# 16_40PIN_Connector.net
KiCad netlist of a schematic drawn in Altium Designer
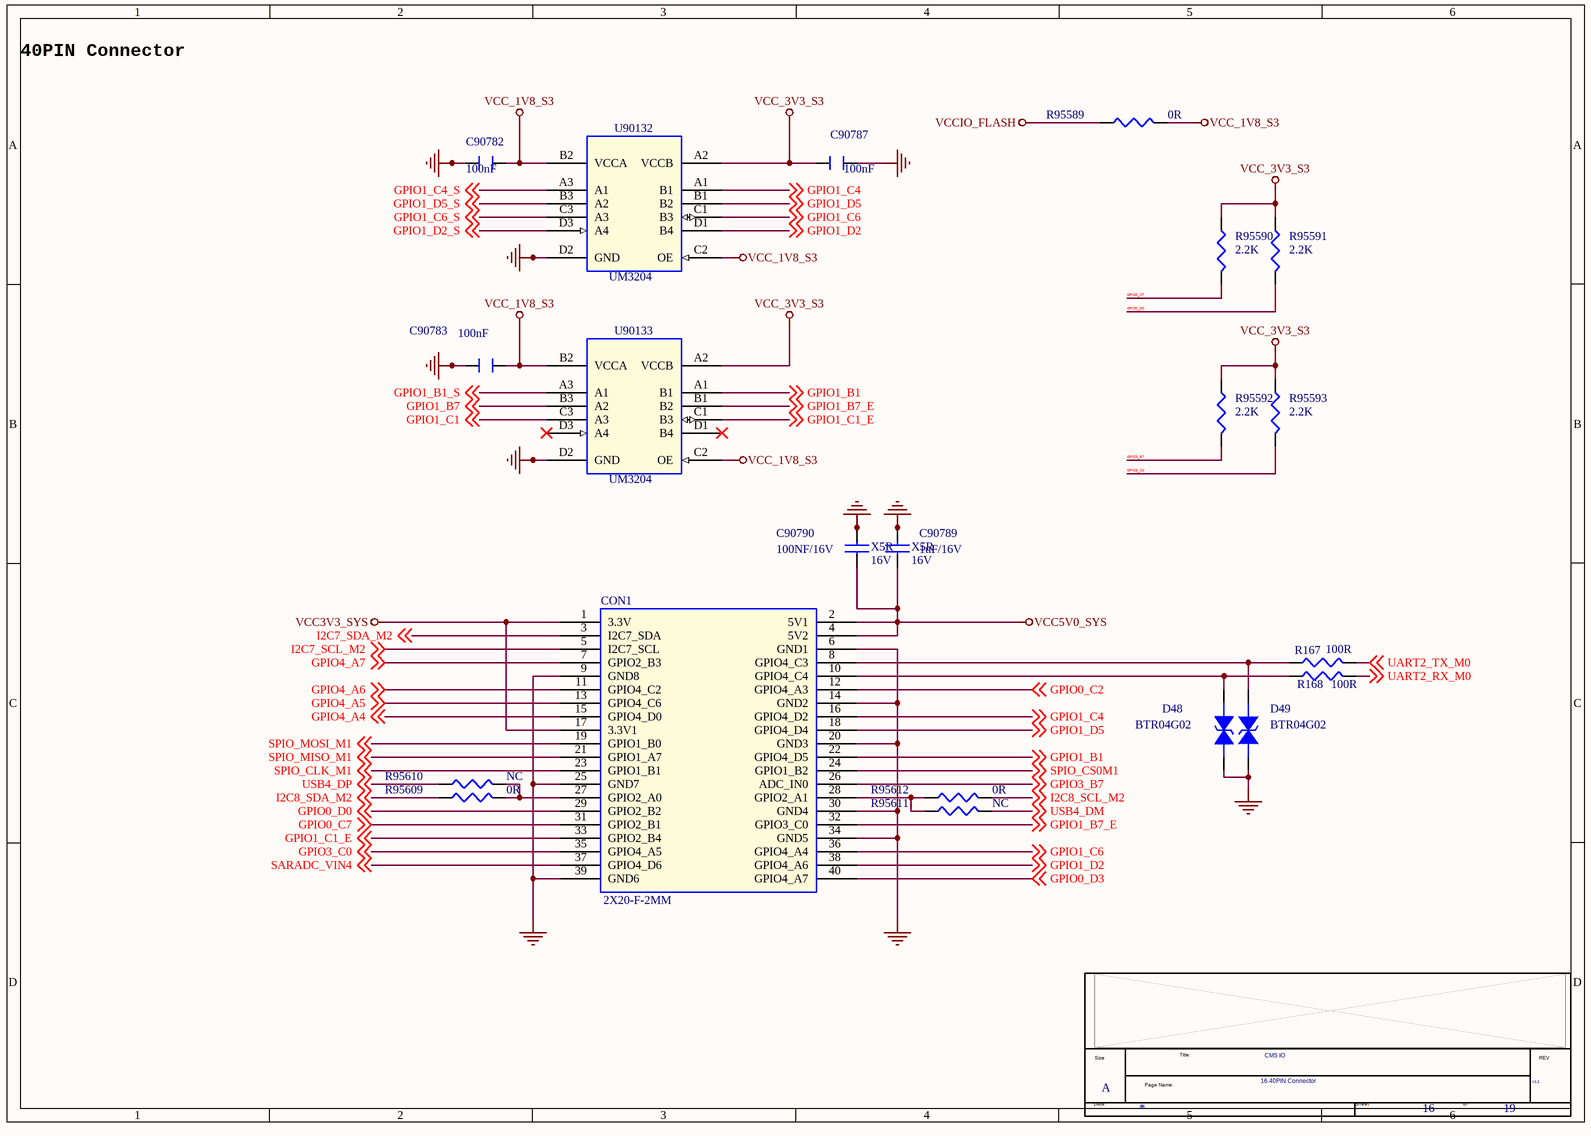
[diagram p0: 16_40PIN_Connector.SchDoc]

(export (version "E")
  (design (tool "Eeschema 10.0.6"))
  (components
    (comp (ref "*")
      (value "radxa_1010")
      (fields
        (field (name "DOC") "16.40PIN Connector")
        (field (name "REVCODE") "V2.2")
        (field (name "TITLE") "CM5 IO")
        (field (name "PAGE SIZE") "A")
        (field (name "PAGE NUMBER") "16")
        (field (name "PAGE COUNT") "19")
      )
      (libsource (lib "*") (part "radxa_1010"))
    )
    (comp (ref "C90782") (value "100nF") (footprint "C0402") (libsource (lib "*") (part "CAPACITOR_0")))
    (comp (ref "C90783") (value "100nF") (footprint "C0402") (libsource (lib "*") (part "CAPACITOR_0")))
    (comp (ref "C90787") (value "100nF") (footprint "C0402") (libsource (lib "*") (part "CAPACITOR_0")))
    (comp (ref "C90789")
      (value "1uF/16V")
      (footprint "C0402")
      (description "cap,1.00uF,+/-10%,16V,X5R,C0402")
      (fields
        (field (name "VOLTAGE") "16V")
        (field (name "DIELECTRIC") "X5R")
        (field (name "MANUFACTURER") "TDK")
        (field (name "TOLERANCE") "10%")
        (field (name "CREATED BY") "JJJ")
      )
      (libsource (lib "*") (part "CAP NP_0"))
    )
    (comp (ref "C90790")
      (value "100NF/16V")
      (footprint "C0402")
      (description "cap,100.00nF,+/-10%,16V,X5R,C0402")
      (fields
        (field (name "VOLTAGE") "16V")
        (field (name "DIELECTRIC") "X5R")
        (field (name "TOLERANCE") "10%")
        (field (name "MANUFACTURER") "TDK")
        (field (name "CREATED BY") "JJJ")
      )
      (libsource (lib "*") (part "CAP NP_0"))
    )
    (comp (ref "CON1")
      (value "2X20-F-2MM")
      (footprint "DIP40PIN_2D54MM")
      (libsource (lib "*") (part "CN_0_Dup1"))
    )
    (comp (ref "D48")
      (value "BTR04G02")
      (footprint "ESD0402_1XD5")
      (description "1-Line, Bi-directional, Transient Voltage Suppressors.17.5pF.")
      (fields (field (name "MANUFACTURER") "WillSemi(韦尔半导体)") (field (name "CREATED BY") "JJJ"))
      (libsource (lib "*") (part "DIODE BI_DIR TRIG_2"))
    )
    (comp (ref "D49")
      (value "BTR04G02")
      (footprint "ESD0402_1XD5")
      (description "1-Line, Bi-directional, Transient Voltage Suppressors.17.5pF.")
      (fields (field (name "MANUFACTURER") "WillSemi(韦尔半导体)") (field (name "CREATED BY") "JJJ"))
      (libsource (lib "*") (part "DIODE BI_DIR TRIG_2"))
    )
    (comp (ref "R167")
      (value "100R")
      (footprint "R0402")
      (description "通用厚膜电阻,100R,+/-5%,R0402,1/16W.")
      (fields
        (field (name "TOLERANCE") "5%")
        (field (name "MANUFACTURER") "YAGEO")
        (field (name "CREATED BY") "YTL")
      )
      (libsource (lib "*") (part "RESISTOR_0_Dup3"))
    )
    (comp (ref "R168")
      (value "100R")
      (footprint "R0402")
      (description "通用厚膜电阻,100R,+/-5%,R0402,1/16W.")
      (fields
        (field (name "TOLERANCE") "5%")
        (field (name "MANUFACTURER") "YAGEO")
        (field (name "CREATED BY") "YTL")
      )
      (libsource (lib "*") (part "RESISTOR_0_Dup3"))
    )
    (comp (ref "R95589")
      (value "0R")
      (footprint "R0402")
      (description "通用厚膜电阻,2K2,+/-5%,R0402,1/16W.")
      (fields
        (field (name "TOLERANCE") "5%")
        (field (name "MANUFACTURER") "YAGEO")
        (field (name "CREATED BY") "YTL")
      )
      (libsource (lib "*") (part "RESISTOR_3"))
    )
    (comp (ref "R95590")
      (value "2.2K")
      (footprint "R0402")
      (description "通用厚膜电阻,2K2,+/-5%,R0402,1/16W.")
      (fields
        (field (name "TOLERANCE") "5%")
        (field (name "MANUFACTURER") "YAGEO")
        (field (name "CREATED BY") "YTL")
      )
      (libsource (lib "*") (part "RESISTOR_3"))
    )
    (comp (ref "R95591")
      (value "2.2K")
      (footprint "R0402")
      (description "通用厚膜电阻,2K2,+/-5%,R0402,1/16W.")
      (fields
        (field (name "TOLERANCE") "5%")
        (field (name "MANUFACTURER") "YAGEO")
        (field (name "CREATED BY") "YTL")
      )
      (libsource (lib "*") (part "RESISTOR_3"))
    )
    (comp (ref "R95592")
      (value "2.2K")
      (footprint "R0402")
      (description "通用厚膜电阻,2K2,+/-5%,R0402,1/16W.")
      (fields
        (field (name "TOLERANCE") "5%")
        (field (name "MANUFACTURER") "YAGEO")
        (field (name "CREATED BY") "YTL")
      )
      (libsource (lib "*") (part "RESISTOR_3"))
    )
    (comp (ref "R95593")
      (value "2.2K")
      (footprint "R0402")
      (description "通用厚膜电阻,2K2,+/-5%,R0402,1/16W.")
      (fields
        (field (name "TOLERANCE") "5%")
        (field (name "MANUFACTURER") "YAGEO")
        (field (name "CREATED BY") "YTL")
      )
      (libsource (lib "*") (part "RESISTOR_3"))
    )
    (comp (ref "R95609")
      (value "0R")
      (footprint "R0402")
      (description "通用厚膜电阻,2K2,+/-5%,R0402,1/16W.")
      (fields
        (field (name "TOLERANCE") "5%")
        (field (name "MANUFACTURER") "YAGEO")
        (field (name "CREATED BY") "YTL")
      )
      (libsource (lib "*") (part "RESISTOR_3"))
    )
    (comp (ref "R95610")
      (value "NC")
      (footprint "R0402")
      (description "通用厚膜电阻,2K2,+/-5%,R0402,1/16W.")
      (fields
        (field (name "TOLERANCE") "5%")
        (field (name "MANUFACTURER") "YAGEO")
        (field (name "CREATED BY") "YTL")
      )
      (libsource (lib "*") (part "RESISTOR_3"))
    )
    (comp (ref "R95611")
      (value "NC")
      (footprint "R0402")
      (description "通用厚膜电阻,2K2,+/-5%,R0402,1/16W.")
      (fields
        (field (name "TOLERANCE") "5%")
        (field (name "MANUFACTURER") "YAGEO")
        (field (name "CREATED BY") "YTL")
      )
      (libsource (lib "*") (part "RESISTOR_3"))
    )
    (comp (ref "R95612")
      (value "0R")
      (footprint "R0402")
      (description "通用厚膜电阻,2K2,+/-5%,R0402,1/16W.")
      (fields
        (field (name "TOLERANCE") "5%")
        (field (name "MANUFACTURER") "YAGEO")
        (field (name "CREATED BY") "YTL")
      )
      (libsource (lib "*") (part "RESISTOR_3"))
    )
    (comp (ref "U90132")
      (value "UM3204")
      (footprint "CSP-12")
      (description "4-bit Bi-directional Level Shifter  UM3204H")
      (fields (field (name "PART NUMBER") "PI4ULS5V104GAEX"))
      (libsource (lib "*") (part "MP2610_0"))
    )
    (comp (ref "U90133")
      (value "UM3204")
      (footprint "CSP-12")
      (description "4-bit Bi-directional Level Shifter  UM3204H")
      (fields (field (name "PART NUMBER") "PI4ULS5V104GAEX"))
      (libsource (lib "*") (part "MP2610_0"))
    )
  )
  (nets
    (net (code "1") (name "GND") (class "Default")
      (node (ref "C90782") (pin "1") (pinfunction "1_1") (pintype "passive"))
      (node (ref "C90783") (pin "1") (pinfunction "1_1") (pintype "passive"))
      (node (ref "C90787") (pin "1") (pinfunction "1_1") (pintype "passive"))
      (node (ref "C90789") (pin "2") (pinfunction "2_2") (pintype "passive"))
      (node (ref "C90790") (pin "2") (pinfunction "2_2") (pintype "passive"))
      (node (ref "CON1") (pin "14") (pinfunction "GND2_14") (pintype "passive"))
      (node (ref "CON1") (pin "20") (pinfunction "GND3_20") (pintype "passive"))
      (node (ref "CON1") (pin "25") (pinfunction "GND7_25") (pintype "passive"))
      (node (ref "CON1") (pin "30") (pinfunction "GND4_30") (pintype "passive"))
      (node (ref "CON1") (pin "34") (pinfunction "GND5_34") (pintype "passive"))
      (node (ref "CON1") (pin "39") (pinfunction "GND6_39") (pintype "passive"))
      (node (ref "CON1") (pin "6") (pinfunction "GND1_6") (pintype "passive"))
      (node (ref "CON1") (pin "9") (pinfunction "GND8_9") (pintype "passive"))
      (node (ref "D48") (pin "1") (pinfunction "1_1") (pintype "passive"))
      (node (ref "D49") (pin "1") (pinfunction "1_1") (pintype "passive"))
      (node (ref "U90132") (pin "D2") (pinfunction "GND_D2") (pintype "power_in"))
      (node (ref "U90133") (pin "D2") (pinfunction "GND_D2") (pintype "power_in"))
    )
    (net (code "2") (name "GPIO0_C2") (class "Default")
      (node (ref "CON1") (pin "12") (pinfunction "GPIO4_A3_12") (pintype "passive"))
    )
    (net (code "3") (name "GPIO0_C7") (class "Default")
      (node (ref "CON1") (pin "31") (pinfunction "GPIO2_B1_31") (pintype "passive"))
      (node (ref "R95590") (pin "2") (pinfunction "2_2") (pintype "passive"))
    )
    (net (code "4") (name "GPIO0_D0") (class "Default")
      (node (ref "CON1") (pin "29") (pinfunction "GPIO2_B2_29") (pintype "passive"))
      (node (ref "R95591") (pin "2") (pinfunction "2_2") (pintype "passive"))
    )
    (net (code "5") (name "GPIO0_D3") (class "Default")
      (node (ref "CON1") (pin "40") (pinfunction "GPIO4_A7_40") (pintype "passive"))
    )
    (net (code "6") (name "GPIO1_B1") (class "Default")
      (node (ref "CON1") (pin "22") (pinfunction "GPIO4_D5_22") (pintype "passive"))
      (node (ref "U90133") (pin "A1") (pinfunction "B1_A1") (pintype "tri_state"))
    )
    (net (code "7") (name "GPIO1_B1_S") (class "Default")
      (node (ref "U90133") (pin "A3") (pinfunction "A1_A3") (pintype "tri_state"))
    )
    (net (code "8") (name "GPIO1_B7") (class "Default")
      (node (ref "U90133") (pin "B3") (pinfunction "A2_B3") (pintype "tri_state"))
    )
    (net (code "9") (name "GPIO1_B7_E") (class "Default")
      (node (ref "CON1") (pin "32") (pinfunction "GPIO3_C0_32") (pintype "passive"))
      (node (ref "U90133") (pin "B1") (pinfunction "B2_B1") (pintype "tri_state"))
    )
    (net (code "10") (name "GPIO1_C1") (class "Default")
      (node (ref "U90133") (pin "C3") (pinfunction "A3_C3") (pintype "tri_state"))
    )
    (net (code "11") (name "GPIO1_C1_E") (class "Default")
      (node (ref "CON1") (pin "33") (pinfunction "GPIO2_B4_33") (pintype "passive"))
      (node (ref "U90133") (pin "C1") (pinfunction "B3_C1") (pintype "bidirectional"))
    )
    (net (code "12") (name "GPIO1_C4") (class "Default")
      (node (ref "CON1") (pin "16") (pinfunction "GPIO4_D2_16") (pintype "passive"))
      (node (ref "U90132") (pin "A1") (pinfunction "B1_A1") (pintype "tri_state"))
    )
    (net (code "13") (name "GPIO1_C4_S") (class "Default")
      (node (ref "U90132") (pin "A3") (pinfunction "A1_A3") (pintype "tri_state"))
    )
    (net (code "14") (name "GPIO1_C6") (class "Default")
      (node (ref "CON1") (pin "36") (pinfunction "GPIO4_A4_36") (pintype "passive"))
      (node (ref "U90132") (pin "C1") (pinfunction "B3_C1") (pintype "bidirectional"))
    )
    (net (code "15") (name "GPIO1_C6_S") (class "Default")
      (node (ref "U90132") (pin "C3") (pinfunction "A3_C3") (pintype "tri_state"))
    )
    (net (code "16") (name "GPIO1_D2") (class "Default")
      (node (ref "CON1") (pin "38") (pinfunction "GPIO4_A6_38") (pintype "passive"))
      (node (ref "U90132") (pin "D1") (pinfunction "B4_D1") (pintype "tri_state"))
    )
    (net (code "17") (name "GPIO1_D2_S") (class "Default")
      (node (ref "U90132") (pin "D3") (pinfunction "A4_D3") (pintype "input"))
    )
    (net (code "18") (name "GPIO1_D5") (class "Default")
      (node (ref "CON1") (pin "18") (pinfunction "GPIO4_D4_18") (pintype "passive"))
      (node (ref "U90132") (pin "B1") (pinfunction "B2_B1") (pintype "tri_state"))
    )
    (net (code "19") (name "GPIO1_D5_S") (class "Default")
      (node (ref "U90132") (pin "B3") (pinfunction "A2_B3") (pintype "tri_state"))
    )
    (net (code "20") (name "GPIO3_B7") (class "Default")
      (node (ref "CON1") (pin "26") (pinfunction "ADC_IN0_26") (pintype "passive"))
      (node (ref "R95592") (pin "2") (pinfunction "2_2") (pintype "passive"))
    )
    (net (code "21") (name "GPIO3_C0") (class "Default")
      (node (ref "CON1") (pin "35") (pinfunction "GPIO4_A5_35") (pintype "passive"))
      (node (ref "R95593") (pin "2") (pinfunction "2_2") (pintype "passive"))
    )
    (net (code "22") (name "GPIO4_A4") (class "Default")
      (node (ref "CON1") (pin "15") (pinfunction "GPIO4_D0_15") (pintype "passive"))
    )
    (net (code "23") (name "GPIO4_A5") (class "Default")
      (node (ref "CON1") (pin "13") (pinfunction "GPIO4_C6_13") (pintype "passive"))
    )
    (net (code "24") (name "GPIO4_A6") (class "Default")
      (node (ref "CON1") (pin "11") (pinfunction "GPIO4_C2_11") (pintype "passive"))
    )
    (net (code "25") (name "GPIO4_A7") (class "Default")
      (node (ref "CON1") (pin "7") (pinfunction "GPIO2_B3_7") (pintype "passive"))
    )
    (net (code "26") (name "I2C7_SCL_M2") (class "Default")
      (node (ref "CON1") (pin "5") (pinfunction "I2C7_SCL_5") (pintype "passive"))
    )
    (net (code "27") (name "I2C7_SDA_M2") (class "Default")
      (node (ref "CON1") (pin "3") (pinfunction "I2C7_SDA_3") (pintype "passive"))
    )
    (net (code "28") (name "I2C8_SCL_M2") (class "Default")
      (node (ref "R95612") (pin "2") (pinfunction "2_2") (pintype "passive"))
    )
    (net (code "29") (name "I2C8_SDA_M2") (class "Default")
      (node (ref "R95609") (pin "1") (pinfunction "1_1") (pintype "passive"))
    )
    (net (code "30") (name "Net-(CON1-GPIO2_A0)") (class "Default")
      (node (ref "CON1") (pin "27") (pinfunction "GPIO2_A0_27") (pintype "passive"))
      (node (ref "R95609") (pin "2") (pinfunction "2_2") (pintype "passive"))
      (node (ref "R95610") (pin "2") (pinfunction "2_2") (pintype "passive"))
    )
    (net (code "31") (name "Net-(CON1-GPIO2_A1)") (class "Default")
      (node (ref "CON1") (pin "28") (pinfunction "GPIO2_A1_28") (pintype "passive"))
      (node (ref "R95611") (pin "1") (pinfunction "1_1") (pintype "passive"))
      (node (ref "R95612") (pin "1") (pinfunction "1_1") (pintype "passive"))
    )
    (net (code "32") (name "Net-(CON1-GPIO4_C3)") (class "Default")
      (node (ref "CON1") (pin "8") (pinfunction "GPIO4_C3_8") (pintype "passive"))
      (node (ref "D49") (pin "2") (pinfunction "2_2") (pintype "passive"))
      (node (ref "R167") (pin "1") (pinfunction "1_1") (pintype "passive"))
    )
    (net (code "33") (name "Net-(CON1-GPIO4_C4)") (class "Default")
      (node (ref "CON1") (pin "10") (pinfunction "GPIO4_C4_10") (pintype "passive"))
      (node (ref "D48") (pin "2") (pinfunction "2_2") (pintype "passive"))
      (node (ref "R168") (pin "1") (pinfunction "1_1") (pintype "passive"))
    )
    (net (code "34") (name "SARADC_VIN4") (class "Default")
      (node (ref "CON1") (pin "37") (pinfunction "GPIO4_D6_37") (pintype "passive"))
    )
    (net (code "35") (name "SPIO_CLK_M1") (class "Default")
      (node (ref "CON1") (pin "23") (pinfunction "GPIO1_B1_23") (pintype "passive"))
    )
    (net (code "36") (name "SPIO_CS0M1") (class "Default")
      (node (ref "CON1") (pin "24") (pinfunction "GPIO1_B2_24") (pintype "passive"))
    )
    (net (code "37") (name "SPIO_MISO_M1") (class "Default")
      (node (ref "CON1") (pin "21") (pinfunction "GPIO1_A7_21") (pintype "passive"))
    )
    (net (code "38") (name "SPIO_MOSI_M1") (class "Default")
      (node (ref "CON1") (pin "19") (pinfunction "GPIO1_B0_19") (pintype "passive"))
    )
    (net (code "39") (name "UART2_RX_M0") (class "Default")
      (node (ref "R168") (pin "2") (pinfunction "2_2") (pintype "passive"))
    )
    (net (code "40") (name "UART2_TX_M0") (class "Default")
      (node (ref "R167") (pin "2") (pinfunction "2_2") (pintype "passive"))
    )
    (net (code "41") (name "USB4_DM") (class "Default")
      (node (ref "R95611") (pin "2") (pinfunction "2_2") (pintype "passive"))
    )
    (net (code "42") (name "USB4_DP") (class "Default")
      (node (ref "R95610") (pin "1") (pinfunction "1_1") (pintype "passive"))
    )
    (net (code "43") (name "VCC3V3_SYS") (class "Default")
      (node (ref "CON1") (pin "1") (pinfunction "3.3V_1") (pintype "passive"))
      (node (ref "CON1") (pin "17") (pinfunction "3.3V1_17") (pintype "passive"))
    )
    (net (code "44") (name "VCC5V0_SYS") (class "Default")
      (node (ref "C90789") (pin "1") (pinfunction "1_1") (pintype "passive"))
      (node (ref "C90790") (pin "1") (pinfunction "1_1") (pintype "passive"))
      (node (ref "CON1") (pin "2") (pinfunction "5V1_2") (pintype "passive"))
      (node (ref "CON1") (pin "4") (pinfunction "5V2_4") (pintype "passive"))
    )
    (net (code "45") (name "VCCIO_FLASH") (class "Default")
      (node (ref "R95589") (pin "1") (pinfunction "1_1") (pintype "passive"))
    )
    (net (code "46") (name "VCC_1V8_S3") (class "Default")
      (node (ref "C90782") (pin "2") (pinfunction "2_2") (pintype "passive"))
      (node (ref "C90783") (pin "2") (pinfunction "2_2") (pintype "passive"))
      (node (ref "R95589") (pin "2") (pinfunction "2_2") (pintype "passive"))
      (node (ref "U90132") (pin "B2") (pinfunction "VCCA_B2") (pintype "power_in"))
      (node (ref "U90132") (pin "C2") (pinfunction "OE_C2") (pintype "input"))
      (node (ref "U90133") (pin "B2") (pinfunction "VCCA_B2") (pintype "power_in"))
      (node (ref "U90133") (pin "C2") (pinfunction "OE_C2") (pintype "input"))
    )
    (net (code "47") (name "VCC_3V3_S3") (class "Default")
      (node (ref "C90787") (pin "2") (pinfunction "2_2") (pintype "passive"))
      (node (ref "R95590") (pin "1") (pinfunction "1_1") (pintype "passive"))
      (node (ref "R95591") (pin "1") (pinfunction "1_1") (pintype "passive"))
      (node (ref "R95592") (pin "1") (pinfunction "1_1") (pintype "passive"))
      (node (ref "R95593") (pin "1") (pinfunction "1_1") (pintype "passive"))
      (node (ref "U90132") (pin "A2") (pinfunction "VCCB_A2") (pintype "power_in"))
      (node (ref "U90133") (pin "A2") (pinfunction "VCCB_A2") (pintype "power_in"))
    )
    (net (code "48") (name "unconnected-(U90133-A4-PadD3)") (class "Default")
      (node (ref "U90133") (pin "D3") (pinfunction "A4_D3") (pintype "input+no_connect"))
    )
    (net (code "49") (name "unconnected-(U90133-B4-PadD1)") (class "Default")
      (node (ref "U90133") (pin "D1") (pinfunction "B4_D1") (pintype "tri_state+no_connect"))
    )
  )
)
